# OBC_Connectors_Piggyback.net
KiCad netlist of a schematic drawn in Altium Designer
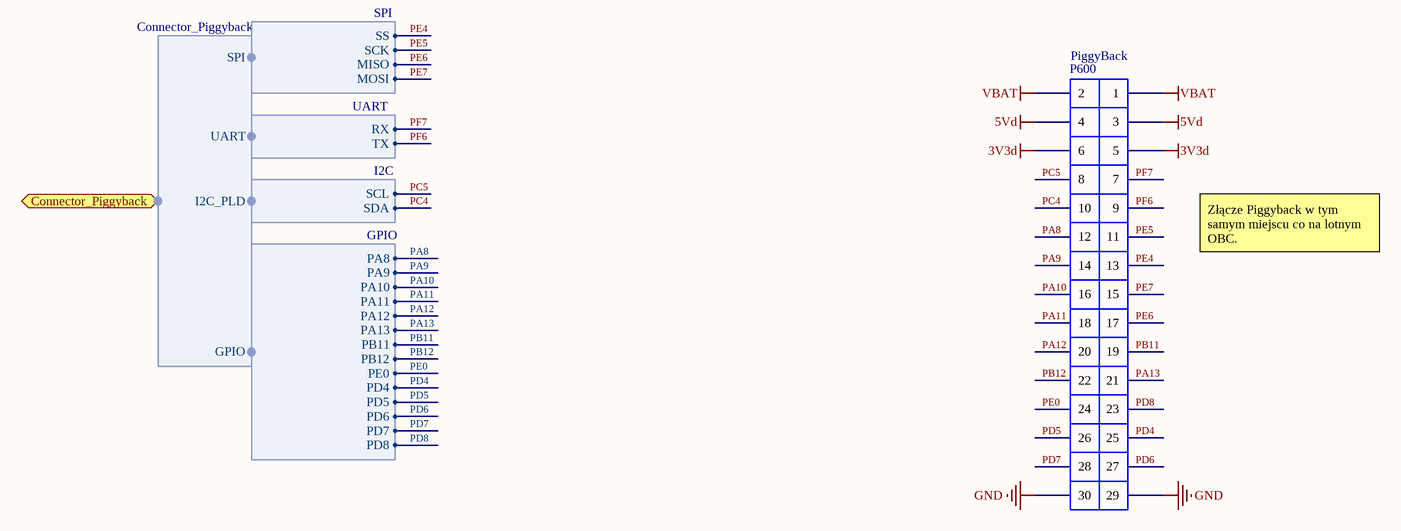
[diagram p0: OBC_Connectors_Piggyback.SchDoc]

(export (version "E")
  (design (tool "Eeschema 10.0.6"))
  (components
    (comp (ref "P600")
      (value "PiggyBack")
      (footprint "Samtec_CES-115-01-L-D")
      (description "Low Profile Socket Strips")
      (fields (field (name "PARTNO") "CES-115-01-G-D") (field (name "MANUFACTURER") "Samtec"))
      (libsource (lib "connectors_printed-circuit-board") (part "Samtec_CES-115-xx-x-D"))
    )
  )
  (nets
    (net (code "2") (name "/PA8") (class "Default")
      (node (ref "P600") (pin "12") (pinfunction "12_12") (pintype "passive"))
    )
    (net (code "3") (name "/PA9") (class "Default")
      (node (ref "P600") (pin "14") (pinfunction "14_14") (pintype "passive"))
    )
    (net (code "4") (name "/PA10") (class "Default")
      (node (ref "P600") (pin "16") (pinfunction "16_16") (pintype "passive"))
    )
    (net (code "5") (name "/PA11") (class "Default")
      (node (ref "P600") (pin "18") (pinfunction "18_18") (pintype "passive"))
    )
    (net (code "6") (name "/PA12") (class "Default")
      (node (ref "P600") (pin "20") (pinfunction "20_20") (pintype "passive"))
    )
    (net (code "7") (name "/PA13") (class "Default")
      (node (ref "P600") (pin "21") (pinfunction "21_21") (pintype "passive"))
    )
    (net (code "8") (name "/PB11") (class "Default")
      (node (ref "P600") (pin "19") (pinfunction "19_19") (pintype "passive"))
    )
    (net (code "9") (name "/PB12") (class "Default")
      (node (ref "P600") (pin "22") (pinfunction "22_22") (pintype "passive"))
    )
    (net (code "10") (name "/PC4") (class "Default")
      (node (ref "P600") (pin "10") (pinfunction "10_10") (pintype "passive"))
    )
    (net (code "11") (name "/PC5") (class "Default")
      (node (ref "P600") (pin "8") (pinfunction "8_8") (pintype "passive"))
    )
    (net (code "12") (name "/PD4") (class "Default")
      (node (ref "P600") (pin "25") (pinfunction "25_25") (pintype "passive"))
    )
    (net (code "13") (name "/PD5") (class "Default")
      (node (ref "P600") (pin "26") (pinfunction "26_26") (pintype "passive"))
    )
    (net (code "14") (name "/PD6") (class "Default")
      (node (ref "P600") (pin "27") (pinfunction "27_27") (pintype "passive"))
    )
    (net (code "15") (name "/PD7") (class "Default")
      (node (ref "P600") (pin "28") (pinfunction "28_28") (pintype "passive"))
    )
    (net (code "16") (name "/PD8") (class "Default")
      (node (ref "P600") (pin "23") (pinfunction "23_23") (pintype "passive"))
    )
    (net (code "17") (name "/PE0") (class "Default")
      (node (ref "P600") (pin "24") (pinfunction "24_24") (pintype "passive"))
    )
    (net (code "18") (name "/PE4") (class "Default")
      (node (ref "P600") (pin "13") (pinfunction "13_13") (pintype "passive"))
    )
    (net (code "19") (name "/PE5") (class "Default")
      (node (ref "P600") (pin "11") (pinfunction "11_11") (pintype "passive"))
    )
    (net (code "20") (name "/PE6") (class "Default")
      (node (ref "P600") (pin "17") (pinfunction "17_17") (pintype "passive"))
    )
    (net (code "21") (name "/PE7") (class "Default")
      (node (ref "P600") (pin "15") (pinfunction "15_15") (pintype "passive"))
    )
    (net (code "22") (name "/PF6") (class "Default")
      (node (ref "P600") (pin "9") (pinfunction "9_9") (pintype "passive"))
    )
    (net (code "23") (name "/PF7") (class "Default")
      (node (ref "P600") (pin "7") (pinfunction "7_7") (pintype "passive"))
    )
    (net (code "25") (name "3V3d") (class "Default")
      (node (ref "P600") (pin "5") (pinfunction "5_5") (pintype "passive"))
      (node (ref "P600") (pin "6") (pinfunction "6_6") (pintype "passive"))
    )
    (net (code "26") (name "5Vd") (class "Default")
      (node (ref "P600") (pin "3") (pinfunction "3_3") (pintype "passive"))
      (node (ref "P600") (pin "4") (pinfunction "4_4") (pintype "passive"))
    )
    (net (code "27") (name "GND") (class "Default")
      (node (ref "P600") (pin "29") (pinfunction "29_29") (pintype "passive"))
      (node (ref "P600") (pin "30") (pinfunction "30_30") (pintype "passive"))
    )
    (net (code "28") (name "VBAT") (class "Default")
      (node (ref "P600") (pin "1") (pinfunction "1_1") (pintype "passive"))
      (node (ref "P600") (pin "2") (pinfunction "2_2") (pintype "passive"))
    )
  )
)
